# DAC_FMC_connector.net
KiCad netlist of a schematic drawn in Altium Designer
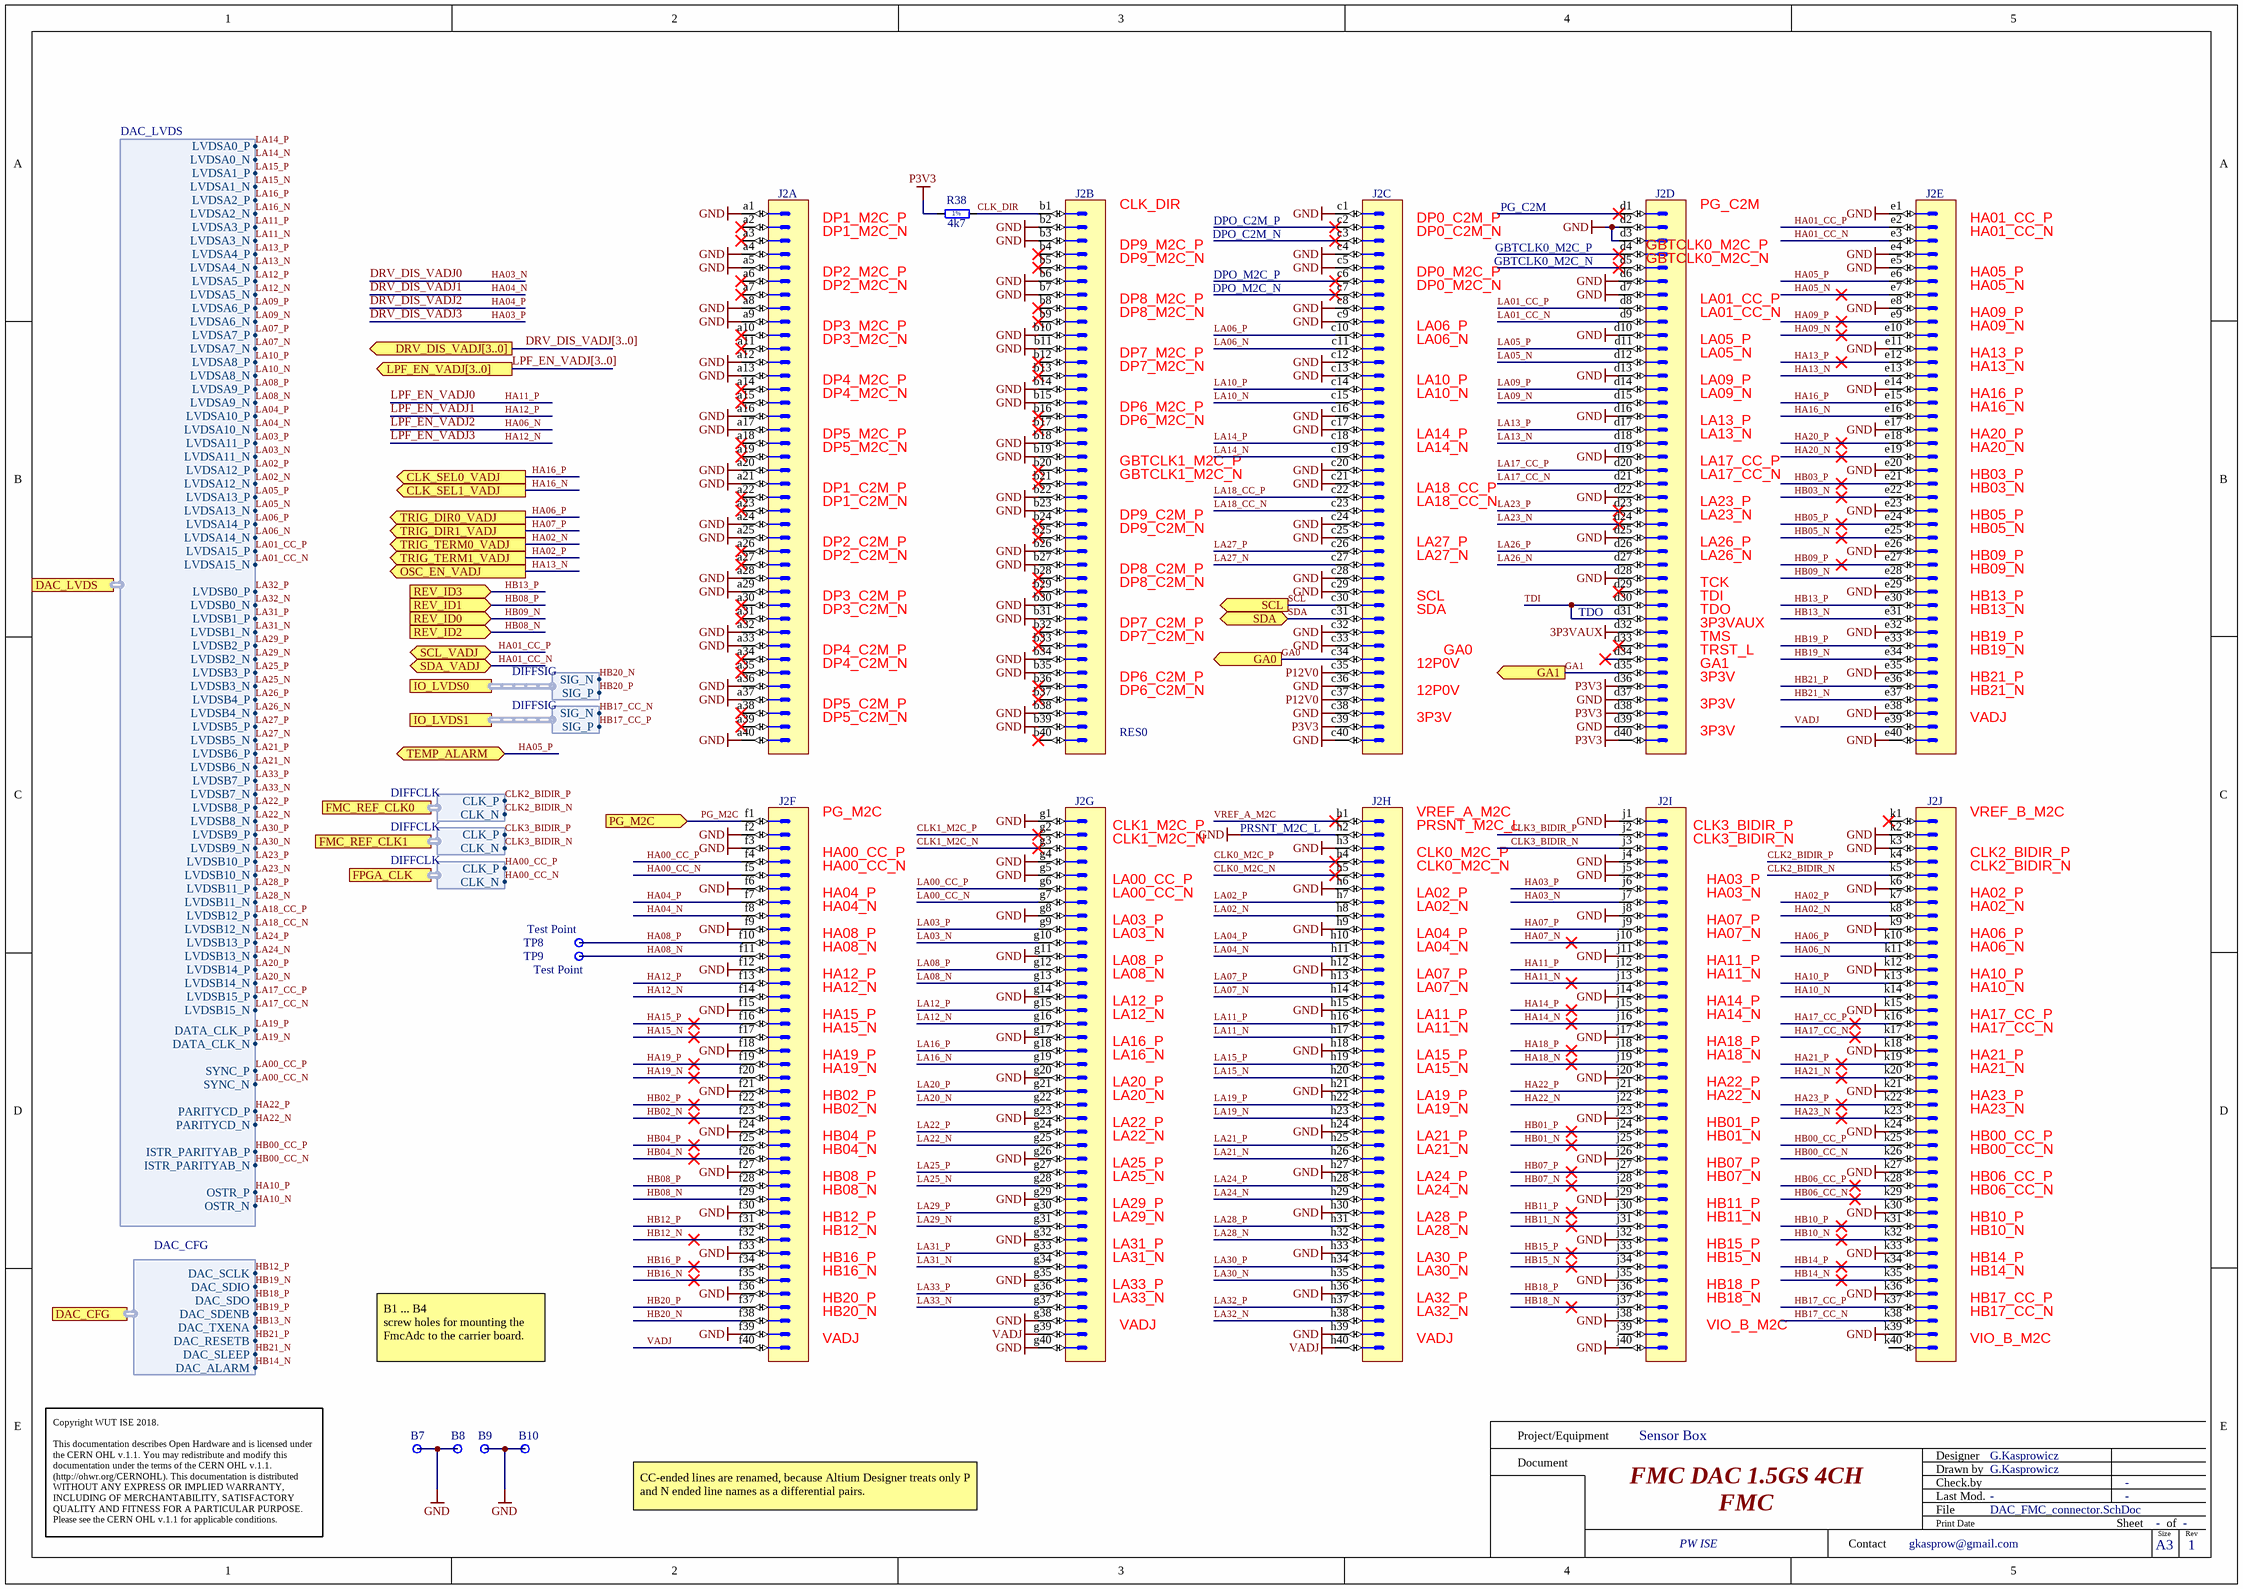
[diagram p0: DAC_FMC_connector.SchDoc]

(export (version "E")
  (design (tool "Eeschema 10.0.6"))
  (components
    (comp (ref "B7")
      (value "Plated Hole")
      (footprint "MTG300_600")
      (description "Single Terminal Socket")
      (fields (field (name "PART NUMBER") "PLATED_HOLE3.0_PAD6.0") (field (name "AUTHOR") "CERN DEM JLC"))
      (libsource (lib "Eletro-mechanical") (part "Single Terminal Socket"))
    )
    (comp (ref "B8")
      (value "Plated Hole")
      (footprint "MTG300_600")
      (description "Single Terminal Socket")
      (fields (field (name "PART NUMBER") "PLATED_HOLE3.0_PAD6.0") (field (name "AUTHOR") "CERN DEM JLC"))
      (libsource (lib "Eletro-mechanical") (part "Single Terminal Socket"))
    )
    (comp (ref "B9")
      (value "Plated Hole")
      (footprint "MTG300_600")
      (description "Single Terminal Socket")
      (fields (field (name "PART NUMBER") "PLATED_HOLE3.0_PAD6.0") (field (name "AUTHOR") "CERN DEM JLC"))
      (libsource (lib "Eletro-mechanical") (part "Single Terminal Socket"))
    )
    (comp (ref "B10")
      (value "Plated Hole")
      (footprint "MTG300_600")
      (description "Single Terminal Socket")
      (fields (field (name "PART NUMBER") "PLATED_HOLE3.0_PAD6.0") (field (name "AUTHOR") "CERN DEM JLC"))
      (libsource (lib "Eletro-mechanical") (part "Single Terminal Socket"))
    )
    (comp (ref "J2")
      (value "VITA 57")
      (footprint "SAMTEC_ASP-134488-01")
      (description "Connector VITA 57, 400 Male contacts in 10 row abcdefghj")
      (fields
        (field (name "PART NUMBER") "SAMTEC_ASP-134488-01")
        (field (name "MANUFACTURER") "SAMTEC")
        (field (name "AUTHOR") "CERN DEM JLC")
      )
      (libsource (lib "Connectors") (part "Connector VITA 57 400 Male (abcdefghjk)"))
    )
    (comp (ref "R38")
      (value "4k7")
      (footprint "RESC1608X55N")
      (description "Resistor - 1%")
      (fields
        (field (name "PART NUMBER") "R0603_4K7_1%_0.1W_100PPM")
        (field (name "POWER") "0.1W")
        (field (name "AUTHOR") "CERN DEM JLC")
      )
      (libsource (lib "Resistors") (part "Resistor - 1%"))
    )
    (comp (ref "TP8")
      (value "Test Point")
      (footprint "TPS127")
      (fields (field (name "PART NUMBER") "SMD_PAD_1.27X1.27MM") (field (name "AUTHOR") "CERN DEM JLC"))
      (libsource (lib "Eletro-mechanical") (part "Test Point"))
    )
    (comp (ref "TP9")
      (value "Test Point")
      (footprint "TPS127")
      (fields (field (name "PART NUMBER") "SMD_PAD_1.27X1.27MM") (field (name "AUTHOR") "CERN DEM JLC"))
      (libsource (lib "Eletro-mechanical") (part "Test Point"))
    )
  )
  (nets
    (net (code "5") (name "/CLK0_M2C_N") (class "Default")
      (node (ref "J2") (pin "h5") (pinfunction "h5_h5") (pintype "bidirectional+no_connect"))
    )
    (net (code "6") (name "/CLK0_M2C_P") (class "Default")
      (node (ref "J2") (pin "h4") (pinfunction "h4_h4") (pintype "bidirectional+no_connect"))
    )
    (net (code "7") (name "/CLK1_M2C_N") (class "Default")
      (node (ref "J2") (pin "g3") (pinfunction "g3_g3") (pintype "bidirectional+no_connect"))
    )
    (net (code "8") (name "/CLK1_M2C_P") (class "Default")
      (node (ref "J2") (pin "g2") (pinfunction "g2_g2") (pintype "bidirectional+no_connect"))
    )
    (net (code "9") (name "/CLK2_BIDIR_N") (class "Default")
      (node (ref "J2") (pin "k5") (pinfunction "k5_k5") (pintype "bidirectional"))
    )
    (net (code "10") (name "/CLK2_BIDIR_P") (class "Default")
      (node (ref "J2") (pin "k4") (pinfunction "k4_k4") (pintype "bidirectional"))
    )
    (net (code "11") (name "/CLK3_BIDIR_N") (class "Default")
      (node (ref "J2") (pin "j3") (pinfunction "j3_j3") (pintype "bidirectional"))
    )
    (net (code "12") (name "/CLK3_BIDIR_P") (class "Default")
      (node (ref "J2") (pin "j2") (pinfunction "j2_j2") (pintype "bidirectional"))
    )
    (net (code "13") (name "/CLK_DIR") (class "Default")
      (node (ref "J2") (pin "b1") (pinfunction "b1_b1") (pintype "bidirectional"))
      (node (ref "R38") (pin "2") (pinfunction "2_2") (pintype "passive"))
    )
    (net (code "14") (name "/DRV_DIS_VADJ0") (class "Default")
      (node (ref "J2") (pin "j7") (pinfunction "j7_j7") (pintype "bidirectional"))
    )
    (net (code "15") (name "/DRV_DIS_VADJ1") (class "Default")
      (node (ref "J2") (pin "f8") (pinfunction "f8_f8") (pintype "bidirectional"))
    )
    (net (code "16") (name "/DRV_DIS_VADJ2") (class "Default")
      (node (ref "J2") (pin "f7") (pinfunction "f7_f7") (pintype "bidirectional"))
    )
    (net (code "17") (name "/DRV_DIS_VADJ3") (class "Default")
      (node (ref "J2") (pin "j6") (pinfunction "j6_j6") (pintype "bidirectional"))
    )
    (net (code "19") (name "/GA0") (class "Default")
      (node (ref "J2") (pin "c34") (pinfunction "c34_c34") (pintype "bidirectional"))
    )
    (net (code "20") (name "/GA1") (class "Default")
      (node (ref "J2") (pin "d35") (pinfunction "d35_d35") (pintype "bidirectional"))
    )
    (net (code "21") (name "/HA00_CC_N") (class "Default")
      (node (ref "J2") (pin "f5") (pinfunction "f5_f5") (pintype "bidirectional"))
    )
    (net (code "22") (name "/HA00_CC_P") (class "Default")
      (node (ref "J2") (pin "f4") (pinfunction "f4_f4") (pintype "bidirectional"))
    )
    (net (code "23") (name "/HA01_CC_N") (class "Default")
      (node (ref "J2") (pin "e3") (pinfunction "e3_e3") (pintype "bidirectional"))
    )
    (net (code "24") (name "/HA01_CC_P") (class "Default")
      (node (ref "J2") (pin "e2") (pinfunction "e2_e2") (pintype "bidirectional"))
    )
    (net (code "25") (name "/HA02_N") (class "Default")
      (node (ref "J2") (pin "k8") (pinfunction "k8_k8") (pintype "bidirectional"))
    )
    (net (code "26") (name "/HA02_P") (class "Default")
      (node (ref "J2") (pin "k7") (pinfunction "k7_k7") (pintype "bidirectional"))
    )
    (net (code "27") (name "/HA05_N") (class "Default")
      (node (ref "J2") (pin "e7") (pinfunction "e7_e7") (pintype "bidirectional"))
    )
    (net (code "28") (name "/HA05_P") (class "Default")
      (node (ref "J2") (pin "e6") (pinfunction "e6_e6") (pintype "bidirectional"))
    )
    (net (code "29") (name "/HA06_P") (class "Default")
      (node (ref "J2") (pin "k10") (pinfunction "k10_k10") (pintype "bidirectional"))
    )
    (net (code "30") (name "/HA07_N") (class "Default")
      (node (ref "J2") (pin "j10") (pinfunction "j10_j10") (pintype "bidirectional"))
    )
    (net (code "31") (name "/HA07_P") (class "Default")
      (node (ref "J2") (pin "j9") (pinfunction "j9_j9") (pintype "bidirectional"))
    )
    (net (code "32") (name "/HA08_N") (class "Default")
      (node (ref "J2") (pin "f11") (pinfunction "f11_f11") (pintype "bidirectional"))
      (node (ref "TP9") (pin "1") (pinfunction "1_1") (pintype "bidirectional"))
    )
    (net (code "33") (name "/HA08_P") (class "Default")
      (node (ref "J2") (pin "f10") (pinfunction "f10_f10") (pintype "bidirectional"))
      (node (ref "TP8") (pin "1") (pinfunction "1_1") (pintype "bidirectional"))
    )
    (net (code "34") (name "/HA09_N") (class "Default")
      (node (ref "J2") (pin "e10") (pinfunction "e10_e10") (pintype "bidirectional"))
    )
    (net (code "35") (name "/HA09_P") (class "Default")
      (node (ref "J2") (pin "e9") (pinfunction "e9_e9") (pintype "bidirectional"))
    )
    (net (code "36") (name "/HA10_N") (class "Default")
      (node (ref "J2") (pin "k14") (pinfunction "k14_k14") (pintype "bidirectional"))
    )
    (net (code "37") (name "/HA10_P") (class "Default")
      (node (ref "J2") (pin "k13") (pinfunction "k13_k13") (pintype "bidirectional"))
    )
    (net (code "38") (name "/HA11_N") (class "Default")
      (node (ref "J2") (pin "j13") (pinfunction "j13_j13") (pintype "bidirectional"))
    )
    (net (code "39") (name "/HA13_N") (class "Default")
      (node (ref "J2") (pin "e13") (pinfunction "e13_e13") (pintype "bidirectional"))
    )
    (net (code "40") (name "/HA13_P") (class "Default")
      (node (ref "J2") (pin "e12") (pinfunction "e12_e12") (pintype "bidirectional"))
    )
    (net (code "41") (name "/HA14_N") (class "Default")
      (node (ref "J2") (pin "j16") (pinfunction "j16_j16") (pintype "bidirectional"))
    )
    (net (code "42") (name "/HA14_P") (class "Default")
      (node (ref "J2") (pin "j15") (pinfunction "j15_j15") (pintype "bidirectional"))
    )
    (net (code "43") (name "/HA15_N") (class "Default")
      (node (ref "J2") (pin "f17") (pinfunction "f17_f17") (pintype "bidirectional"))
    )
    (net (code "44") (name "/HA15_P") (class "Default")
      (node (ref "J2") (pin "f16") (pinfunction "f16_f16") (pintype "bidirectional"))
    )
    (net (code "45") (name "/HA16_N") (class "Default")
      (node (ref "J2") (pin "e16") (pinfunction "e16_e16") (pintype "bidirectional"))
    )
    (net (code "46") (name "/HA16_P") (class "Default")
      (node (ref "J2") (pin "e15") (pinfunction "e15_e15") (pintype "bidirectional"))
    )
    (net (code "47") (name "/HA17_CC_N") (class "Default")
      (node (ref "J2") (pin "k17") (pinfunction "k17_k17") (pintype "bidirectional"))
    )
    (net (code "48") (name "/HA17_CC_P") (class "Default")
      (node (ref "J2") (pin "k16") (pinfunction "k16_k16") (pintype "bidirectional"))
    )
    (net (code "49") (name "/HA18_N") (class "Default")
      (node (ref "J2") (pin "j19") (pinfunction "j19_j19") (pintype "bidirectional"))
    )
    (net (code "50") (name "/HA18_P") (class "Default")
      (node (ref "J2") (pin "j18") (pinfunction "j18_j18") (pintype "bidirectional"))
    )
    (net (code "51") (name "/HA19_N") (class "Default")
      (node (ref "J2") (pin "f20") (pinfunction "f20_f20") (pintype "bidirectional"))
    )
    (net (code "52") (name "/HA19_P") (class "Default")
      (node (ref "J2") (pin "f19") (pinfunction "f19_f19") (pintype "bidirectional"))
    )
    (net (code "53") (name "/HA20_N") (class "Default")
      (node (ref "J2") (pin "e19") (pinfunction "e19_e19") (pintype "bidirectional"))
    )
    (net (code "54") (name "/HA20_P") (class "Default")
      (node (ref "J2") (pin "e18") (pinfunction "e18_e18") (pintype "bidirectional"))
    )
    (net (code "55") (name "/HA21_N") (class "Default")
      (node (ref "J2") (pin "k20") (pinfunction "k20_k20") (pintype "bidirectional"))
    )
    (net (code "56") (name "/HA21_P") (class "Default")
      (node (ref "J2") (pin "k19") (pinfunction "k19_k19") (pintype "bidirectional"))
    )
    (net (code "57") (name "/HA22_N") (class "Default")
      (node (ref "J2") (pin "j22") (pinfunction "j22_j22") (pintype "bidirectional"))
    )
    (net (code "58") (name "/HA22_P") (class "Default")
      (node (ref "J2") (pin "j21") (pinfunction "j21_j21") (pintype "bidirectional"))
    )
    (net (code "59") (name "/HA23_N") (class "Default")
      (node (ref "J2") (pin "k23") (pinfunction "k23_k23") (pintype "bidirectional"))
    )
    (net (code "60") (name "/HA23_P") (class "Default")
      (node (ref "J2") (pin "k22") (pinfunction "k22_k22") (pintype "bidirectional"))
    )
    (net (code "61") (name "/HB00_CC_N") (class "Default")
      (node (ref "J2") (pin "k26") (pinfunction "k26_k26") (pintype "bidirectional"))
    )
    (net (code "62") (name "/HB00_CC_P") (class "Default")
      (node (ref "J2") (pin "k25") (pinfunction "k25_k25") (pintype "bidirectional"))
    )
    (net (code "63") (name "/HB01_N") (class "Default")
      (node (ref "J2") (pin "j25") (pinfunction "j25_j25") (pintype "bidirectional"))
    )
    (net (code "64") (name "/HB01_P") (class "Default")
      (node (ref "J2") (pin "j24") (pinfunction "j24_j24") (pintype "bidirectional"))
    )
    (net (code "65") (name "/HB02_N") (class "Default")
      (node (ref "J2") (pin "f23") (pinfunction "f23_f23") (pintype "bidirectional"))
    )
    (net (code "66") (name "/HB02_P") (class "Default")
      (node (ref "J2") (pin "f22") (pinfunction "f22_f22") (pintype "bidirectional"))
    )
    (net (code "67") (name "/HB03_N") (class "Default")
      (node (ref "J2") (pin "e22") (pinfunction "e22_e22") (pintype "bidirectional"))
    )
    (net (code "68") (name "/HB03_P") (class "Default")
      (node (ref "J2") (pin "e21") (pinfunction "e21_e21") (pintype "bidirectional"))
    )
    (net (code "69") (name "/HB04_N") (class "Default")
      (node (ref "J2") (pin "f26") (pinfunction "f26_f26") (pintype "bidirectional"))
    )
    (net (code "70") (name "/HB04_P") (class "Default")
      (node (ref "J2") (pin "f25") (pinfunction "f25_f25") (pintype "bidirectional"))
    )
    (net (code "71") (name "/HB05_N") (class "Default")
      (node (ref "J2") (pin "e25") (pinfunction "e25_e25") (pintype "bidirectional"))
    )
    (net (code "72") (name "/HB05_P") (class "Default")
      (node (ref "J2") (pin "e24") (pinfunction "e24_e24") (pintype "bidirectional"))
    )
    (net (code "73") (name "/HB06_CC_N") (class "Default")
      (node (ref "J2") (pin "k29") (pinfunction "k29_k29") (pintype "bidirectional"))
    )
    (net (code "74") (name "/HB06_CC_P") (class "Default")
      (node (ref "J2") (pin "k28") (pinfunction "k28_k28") (pintype "bidirectional"))
    )
    (net (code "75") (name "/HB07_N") (class "Default")
      (node (ref "J2") (pin "j28") (pinfunction "j28_j28") (pintype "bidirectional"))
    )
    (net (code "76") (name "/HB07_P") (class "Default")
      (node (ref "J2") (pin "j27") (pinfunction "j27_j27") (pintype "bidirectional"))
    )
    (net (code "77") (name "/HB08_N") (class "Default")
      (node (ref "J2") (pin "f29") (pinfunction "f29_f29") (pintype "bidirectional"))
    )
    (net (code "78") (name "/HB08_P") (class "Default")
      (node (ref "J2") (pin "f28") (pinfunction "f28_f28") (pintype "bidirectional"))
    )
    (net (code "79") (name "/HB09_N") (class "Default")
      (node (ref "J2") (pin "e28") (pinfunction "e28_e28") (pintype "bidirectional"))
    )
    (net (code "80") (name "/HB09_P") (class "Default")
      (node (ref "J2") (pin "e27") (pinfunction "e27_e27") (pintype "bidirectional"))
    )
    (net (code "81") (name "/HB10_N") (class "Default")
      (node (ref "J2") (pin "k32") (pinfunction "k32_k32") (pintype "bidirectional"))
    )
    (net (code "82") (name "/HB10_P") (class "Default")
      (node (ref "J2") (pin "k31") (pinfunction "k31_k31") (pintype "bidirectional"))
    )
    (net (code "83") (name "/HB11_N") (class "Default")
      (node (ref "J2") (pin "j31") (pinfunction "j31_j31") (pintype "bidirectional"))
    )
    (net (code "84") (name "/HB11_P") (class "Default")
      (node (ref "J2") (pin "j30") (pinfunction "j30_j30") (pintype "bidirectional"))
    )
    (net (code "85") (name "/HB12_N") (class "Default")
      (node (ref "J2") (pin "f32") (pinfunction "f32_f32") (pintype "bidirectional"))
    )
    (net (code "86") (name "/HB12_P") (class "Default")
      (node (ref "J2") (pin "f31") (pinfunction "f31_f31") (pintype "bidirectional"))
    )
    (net (code "87") (name "/HB13_N") (class "Default")
      (node (ref "J2") (pin "e31") (pinfunction "e31_e31") (pintype "bidirectional"))
    )
    (net (code "88") (name "/HB13_P") (class "Default")
      (node (ref "J2") (pin "e30") (pinfunction "e30_e30") (pintype "bidirectional"))
    )
    (net (code "89") (name "/HB14_N") (class "Default")
      (node (ref "J2") (pin "k35") (pinfunction "k35_k35") (pintype "bidirectional"))
    )
    (net (code "90") (name "/HB14_P") (class "Default")
      (node (ref "J2") (pin "k34") (pinfunction "k34_k34") (pintype "bidirectional"))
    )
    (net (code "91") (name "/HB15_N") (class "Default")
      (node (ref "J2") (pin "j34") (pinfunction "j34_j34") (pintype "bidirectional"))
    )
    (net (code "92") (name "/HB15_P") (class "Default")
      (node (ref "J2") (pin "j33") (pinfunction "j33_j33") (pintype "bidirectional"))
    )
    (net (code "93") (name "/HB16_N") (class "Default")
      (node (ref "J2") (pin "f35") (pinfunction "f35_f35") (pintype "bidirectional"))
    )
    (net (code "94") (name "/HB16_P") (class "Default")
      (node (ref "J2") (pin "f34") (pinfunction "f34_f34") (pintype "bidirectional"))
    )
    (net (code "95") (name "/HB17_CC_N") (class "Default")
      (node (ref "J2") (pin "k38") (pinfunction "k38_k38") (pintype "bidirectional"))
    )
    (net (code "96") (name "/HB17_CC_P") (class "Default")
      (node (ref "J2") (pin "k37") (pinfunction "k37_k37") (pintype "bidirectional"))
    )
    (net (code "97") (name "/HB18_N") (class "Default")
      (node (ref "J2") (pin "j37") (pinfunction "j37_j37") (pintype "bidirectional"))
    )
    (net (code "98") (name "/HB18_P") (class "Default")
      (node (ref "J2") (pin "j36") (pinfunction "j36_j36") (pintype "bidirectional"))
    )
    (net (code "99") (name "/HB19_N") (class "Default")
      (node (ref "J2") (pin "e34") (pinfunction "e34_e34") (pintype "bidirectional"))
    )
    (net (code "100") (name "/HB19_P") (class "Default")
      (node (ref "J2") (pin "e33") (pinfunction "e33_e33") (pintype "bidirectional"))
    )
    (net (code "101") (name "/HB20_N") (class "Default")
      (node (ref "J2") (pin "f38") (pinfunction "f38_f38") (pintype "bidirectional"))
    )
    (net (code "102") (name "/HB20_P") (class "Default")
      (node (ref "J2") (pin "f37") (pinfunction "f37_f37") (pintype "bidirectional"))
    )
    (net (code "103") (name "/HB21_N") (class "Default")
      (node (ref "J2") (pin "e37") (pinfunction "e37_e37") (pintype "bidirectional"))
    )
    (net (code "104") (name "/HB21_P") (class "Default")
      (node (ref "J2") (pin "e36") (pinfunction "e36_e36") (pintype "bidirectional"))
    )
    (net (code "105") (name "/LA00_CC_N") (class "Default")
      (node (ref "J2") (pin "g7") (pinfunction "g7_g7") (pintype "bidirectional"))
    )
    (net (code "106") (name "/LA00_CC_P") (class "Default")
      (node (ref "J2") (pin "g6") (pinfunction "g6_g6") (pintype "bidirectional"))
    )
    (net (code "107") (name "/LA01_CC_N") (class "Default")
      (node (ref "J2") (pin "d9") (pinfunction "d9_d9") (pintype "bidirectional"))
    )
    (net (code "108") (name "/LA01_CC_P") (class "Default")
      (node (ref "J2") (pin "d8") (pinfunction "d8_d8") (pintype "bidirectional"))
    )
    (net (code "109") (name "/LA02_N") (class "Default")
      (node (ref "J2") (pin "h8") (pinfunction "h8_h8") (pintype "bidirectional"))
    )
    (net (code "110") (name "/LA02_P") (class "Default")
      (node (ref "J2") (pin "h7") (pinfunction "h7_h7") (pintype "bidirectional"))
    )
    (net (code "111") (name "/LA03_N") (class "Default")
      (node (ref "J2") (pin "g10") (pinfunction "g10_g10") (pintype "bidirectional"))
    )
    (net (code "112") (name "/LA03_P") (class "Default")
      (node (ref "J2") (pin "g9") (pinfunction "g9_g9") (pintype "bidirectional"))
    )
    (net (code "113") (name "/LA04_N") (class "Default")
      (node (ref "J2") (pin "h11") (pinfunction "h11_h11") (pintype "bidirectional"))
    )
    (net (code "114") (name "/LA04_P") (class "Default")
      (node (ref "J2") (pin "h10") (pinfunction "h10_h10") (pintype "bidirectional"))
    )
    (net (code "115") (name "/LA05_N") (class "Default")
      (node (ref "J2") (pin "d12") (pinfunction "d12_d12") (pintype "bidirectional"))
    )
    (net (code "116") (name "/LA05_P") (class "Default")
      (node (ref "J2") (pin "d11") (pinfunction "d11_d11") (pintype "bidirectional"))
    )
    (net (code "117") (name "/LA06_N") (class "Default")
      (node (ref "J2") (pin "c11") (pinfunction "c11_c11") (pintype "bidirectional"))
    )
    (net (code "118") (name "/LA06_P") (class "Default")
      (node (ref "J2") (pin "c10") (pinfunction "c10_c10") (pintype "bidirectional"))
    )
    (net (code "119") (name "/LA07_N") (class "Default")
      (node (ref "J2") (pin "h14") (pinfunction "h14_h14") (pintype "bidirectional"))
    )
    (net (code "120") (name "/LA07_P") (class "Default")
      (node (ref "J2") (pin "h13") (pinfunction "h13_h13") (pintype "bidirectional"))
    )
    (net (code "121") (name "/LA08_N") (class "Default")
      (node (ref "J2") (pin "g13") (pinfunction "g13_g13") (pintype "bidirectional"))
    )
    (net (code "122") (name "/LA08_P") (class "Default")
      (node (ref "J2") (pin "g12") (pinfunction "g12_g12") (pintype "bidirectional"))
    )
    (net (code "123") (name "/LA09_N") (class "Default")
      (node (ref "J2") (pin "d15") (pinfunction "d15_d15") (pintype "bidirectional"))
    )
    (net (code "124") (name "/LA09_P") (class "Default")
      (node (ref "J2") (pin "d14") (pinfunction "d14_d14") (pintype "bidirectional"))
    )
    (net (code "125") (name "/LA10_N") (class "Default")
      (node (ref "J2") (pin "c15") (pinfunction "c15_c15") (pintype "bidirectional"))
    )
    (net (code "126") (name "/LA10_P") (class "Default")
      (node (ref "J2") (pin "c14") (pinfunction "c14_c14") (pintype "bidirectional"))
    )
    (net (code "127") (name "/LA11_N") (class "Default")
      (node (ref "J2") (pin "h17") (pinfunction "h17_h17") (pintype "bidirectional"))
    )
    (net (code "128") (name "/LA11_P") (class "Default")
      (node (ref "J2") (pin "h16") (pinfunction "h16_h16") (pintype "bidirectional"))
    )
    (net (code "129") (name "/LA12_N") (class "Default")
      (node (ref "J2") (pin "g16") (pinfunction "g16_g16") (pintype "bidirectional"))
    )
    (net (code "130") (name "/LA12_P") (class "Default")
      (node (ref "J2") (pin "g15") (pinfunction "g15_g15") (pintype "bidirectional"))
    )
    (net (code "131") (name "/LA13_N") (class "Default")
      (node (ref "J2") (pin "d18") (pinfunction "d18_d18") (pintype "bidirectional"))
    )
    (net (code "132") (name "/LA13_P") (class "Default")
      (node (ref "J2") (pin "d17") (pinfunction "d17_d17") (pintype "bidirectional"))
    )
    (net (code "133") (name "/LA14_N") (class "Default")
      (node (ref "J2") (pin "c19") (pinfunction "c19_c19") (pintype "bidirectional"))
    )
    (net (code "134") (name "/LA14_P") (class "Default")
      (node (ref "J2") (pin "c18") (pinfunction "c18_c18") (pintype "bidirectional"))
    )
    (net (code "135") (name "/LA15_N") (class "Default")
      (node (ref "J2") (pin "h20") (pinfunction "h20_h20") (pintype "bidirectional"))
    )
    (net (code "136") (name "/LA15_P") (class "Default")
      (node (ref "J2") (pin "h19") (pinfunction "h19_h19") (pintype "bidirectional"))
    )
    (net (code "137") (name "/LA16_N") (class "Default")
      (node (ref "J2") (pin "g19") (pinfunction "g19_g19") (pintype "bidirectional"))
    )
    (net (code "138") (name "/LA16_P") (class "Default")
      (node (ref "J2") (pin "g18") (pinfunction "g18_g18") (pintype "bidirectional"))
    )
    (net (code "139") (name "/LA17_CC_N") (class "Default")
      (node (ref "J2") (pin "d21") (pinfunction "d21_d21") (pintype "bidirectional"))
    )
    (net (code "140") (name "/LA17_CC_P") (class "Default")
      (node (ref "J2") (pin "d20") (pinfunction "d20_d20") (pintype "bidirectional"))
    )
    (net (code "141") (name "/LA18_CC_N") (class "Default")
      (node (ref "J2") (pin "c23") (pinfunction "c23_c23") (pintype "bidirectional"))
    )
    (net (code "142") (name "/LA18_CC_P") (class "Default")
      (node (ref "J2") (pin "c22") (pinfunction "c22_c22") (pintype "bidirectional"))
    )
    (net (code "143") (name "/LA19_N") (class "Default")
      (node (ref "J2") (pin "h23") (pinfunction "h23_h23") (pintype "bidirectional"))
    )
    (net (code "144") (name "/LA19_P") (class "Default")
      (node (ref "J2") (pin "h22") (pinfunction "h22_h22") (pintype "bidirectional"))
    )
    (net (code "145") (name "/LA20_N") (class "Default")
      (node (ref "J2") (pin "g22") (pinfunction "g22_g22") (pintype "bidirectional"))
    )
    (net (code "146") (name "/LA20_P") (class "Default")
      (node (ref "J2") (pin "g21") (pinfunction "g21_g21") (pintype "bidirectional"))
    )
    (net (code "147") (name "/LA21_N") (class "Default")
      (node (ref "J2") (pin "h26") (pinfunction "h26_h26") (pintype "bidirectional"))
    )
    (net (code "148") (name "/LA21_P") (class "Default")
      (node (ref "J2") (pin "h25") (pinfunction "h25_h25") (pintype "bidirectional"))
    )
    (net (code "149") (name "/LA22_N") (class "Default")
      (node (ref "J2") (pin "g25") (pinfunction "g25_g25") (pintype "bidirectional"))
    )
    (net (code "150") (name "/LA22_P") (class "Default")
      (node (ref "J2") (pin "g24") (pinfunction "g24_g24") (pintype "bidirectional"))
    )
    (net (code "151") (name "/LA23_N") (class "Default")
      (node (ref "J2") (pin "d24") (pinfunction "d24_d24") (pintype "bidirectional"))
    )
    (net (code "152") (name "/LA23_P") (class "Default")
      (node (ref "J2") (pin "d23") (pinfunction "d23_d23") (pintype "bidirectional"))
    )
    (net (code "153") (name "/LA24_N") (class "Default")
      (node (ref "J2") (pin "h29") (pinfunction "h29_h29") (pintype "bidirectional"))
    )
    (net (code "154") (name "/LA24_P") (class "Default")
      (node (ref "J2") (pin "h28") (pinfunction "h28_h28") (pintype "bidirectional"))
    )
    (net (code "155") (name "/LA25_N") (class "Default")
      (node (ref "J2") (pin "g28") (pinfunction "g28_g28") (pintype "bidirectional"))
    )
    (net (code "156") (name "/LA25_P") (class "Default")
      (node (ref "J2") (pin "g27") (pinfunction "g27_g27") (pintype "bidirectional"))
    )
    (net (code "157") (name "/LA26_N") (class "Default")
      (node (ref "J2") (pin "d27") (pinfunction "d27_d27") (pintype "bidirectional"))
    )
    (net (code "158") (name "/LA26_P") (class "Default")
      (node (ref "J2") (pin "d26") (pinfunction "d26_d26") (pintype "bidirectional"))
    )
    (net (code "159") (name "/LA27_N") (class "Default")
      (node (ref "J2") (pin "c27") (pinfunction "c27_c27") (pintype "bidirectional"))
    )
    (net (code "160") (name "/LA27_P") (class "Default")
      (node (ref "J2") (pin "c26") (pinfunction "c26_c26") (pintype "bidirectional"))
    )
    (net (code "161") (name "/LA28_N") (class "Default")
      (node (ref "J2") (pin "h32") (pinfunction "h32_h32") (pintype "bidirectional"))
    )
    (net (code "162") (name "/LA28_P") (class "Default")
      (node (ref "J2") (pin "h31") (pinfunction "h31_h31") (pintype "bidirectional"))
    )
    (net (code "163") (name "/LA29_N") (class "Default")
      (node (ref "J2") (pin "g31") (pinfunction "g31_g31") (pintype "bidirectional"))
    )
    (net (code "164") (name "/LA29_P") (class "Default")
      (node (ref "J2") (pin "g30") (pinfunction "g30_g30") (pintype "bidirectional"))
    )
    (net (code "165") (name "/LA30_N") (class "Default")
      (node (ref "J2") (pin "h35") (pinfunction "h35_h35") (pintype "bidirectional"))
    )
    (net (code "166") (name "/LA30_P") (class "Default")
      (node (ref "J2") (pin "h34") (pinfunction "h34_h34") (pintype "bidirectional"))
    )
    (net (code "167") (name "/LA31_N") (class "Default")
      (node (ref "J2") (pin "g34") (pinfunction "g34_g34") (pintype "bidirectional"))
    )
    (net (code "168") (name "/LA31_P") (class "Default")
      (node (ref "J2") (pin "g33") (pinfunction "g33_g33") (pintype "bidirectional"))
    )
    (net (code "169") (name "/LA32_N") (class "Default")
      (node (ref "J2") (pin "h38") (pinfunction "h38_h38") (pintype "bidirectional"))
    )
    (net (code "170") (name "/LA32_P") (class "Default")
      (node (ref "J2") (pin "h37") (pinfunction "h37_h37") (pintype "bidirectional"))
    )
    (net (code "171") (name "/LA33_N") (class "Default")
      (node (ref "J2") (pin "g37") (pinfunction "g37_g37") (pintype "bidirectional"))
    )
    (net (code "172") (name "/LA33_P") (class "Default")
      (node (ref "J2") (pin "g36") (pinfunction "g36_g36") (pintype "bidirectional"))
    )
    (net (code "173") (name "/LPF_EN_VADJ0") (class "Default")
      (node (ref "J2") (pin "j12") (pinfunction "j12_j12") (pintype "bidirectional"))
    )
    (net (code "174") (name "/LPF_EN_VADJ1") (class "Default")
      (node (ref "J2") (pin "f13") (pinfunction "f13_f13") (pintype "bidirectional"))
    )
    (net (code "175") (name "/LPF_EN_VADJ2") (class "Default")
      (node (ref "J2") (pin "k11") (pinfunction "k11_k11") (pintype "bidirectional"))
    )
    (net (code "176") (name "/LPF_EN_VADJ3") (class "Default")
      (node (ref "J2") (pin "f14") (pinfunction "f14_f14") (pintype "bidirectional"))
    )
    (net (code "178") (name "/PG_M2C") (class "Default")
      (node (ref "J2") (pin "f1") (pinfunction "f1_f1") (pintype "bidirectional"))
    )
    (net (code "179") (name "/SCL") (class "Default")
      (node (ref "J2") (pin "c30") (pinfunction "c30_c30") (pintype "bidirectional"))
    )
    (net (code "180") (name "/SDA") (class "Default")
      (node (ref "J2") (pin "c31") (pinfunction "c31_c31") (pintype "bidirectional"))
    )
    (net (code "181") (name "/TDI") (class "Default")
      (node (ref "J2") (pin "d30") (pinfunction "d30_d30") (pintype "bidirectional"))
      (node (ref "J2") (pin "d31") (pinfunction "d31_d31") (pintype "bidirectional"))
    )
    (net (code "182") (name "/VREF_A_M2C") (class "Default")
      (node (ref "J2") (pin "h1") (pinfunction "h1_h1") (pintype "bidirectional+no_connect"))
    )
    (net (code "187") (name "3P3VAUX") (class "Default")
      (node (ref "J2") (pin "d32") (pinfunction "d32_d32") (pintype "bidirectional"))
    )
    (net (code "188") (name "GND") (class "Default")
      (node (ref "B10") (pin "1") (pinfunction "1_1") (pintype "bidirectional"))
      (node (ref "B7") (pin "1") (pinfunction "1_1") (pintype "bidirectional"))
      (node (ref "B8") (pin "1") (pinfunction "1_1") (pintype "bidirectional"))
      (node (ref "B9") (pin "1") (pinfunction "1_1") (pintype "bidirectional"))
      (node (ref "J2") (pin "a1") (pinfunction "a1_a1") (pintype "bidirectional"))
      (node (ref "J2") (pin "a12") (pinfunction "a12_a12") (pintype "bidirectional"))
      (node (ref "J2") (pin "a13") (pinfunction "a13_a13") (pintype "bidirectional"))
      (node (ref "J2") (pin "a16") (pinfunction "a16_a16") (pintype "bidirectional"))
      (node (ref "J2") (pin "a17") (pinfunction "a17_a17") (pintype "bidirectional"))
      (node (ref "J2") (pin "a20") (pinfunction "a20_a20") (pintype "bidirectional"))
      (node (ref "J2") (pin "a21") (pinfunction "a21_a21") (pintype "bidirectional"))
      (node (ref "J2") (pin "a24") (pinfunction "a24_a24") (pintype "bidirectional"))
      (node (ref "J2") (pin "a25") (pinfunction "a25_a25") (pintype "bidirectional"))
      (node (ref "J2") (pin "a28") (pinfunction "a28_a28") (pintype "bidirectional"))
      (node (ref "J2") (pin "a29") (pinfunction "a29_a29") (pintype "bidirectional"))
      (node (ref "J2") (pin "a32") (pinfunction "a32_a32") (pintype "bidirectional"))
      (node (ref "J2") (pin "a33") (pinfunction "a33_a33") (pintype "bidirectional"))
      (node (ref "J2") (pin "a36") (pinfunction "a36_a36") (pintype "bidirectional"))
      (node (ref "J2") (pin "a37") (pinfunction "a37_a37") (pintype "bidirectional"))
      (node (ref "J2") (pin "a4") (pinfunction "a4_a4") (pintype "bidirectional"))
      (node (ref "J2") (pin "a40") (pinfunction "a40_a40") (pintype "bidirectional"))
      (node (ref "J2") (pin "a5") (pinfunction "a5_a5") (pintype "bidirectional"))
      (node (ref "J2") (pin "a8") (pinfunction "a8_a8") (pintype "bidirectional"))
      (node (ref "J2") (pin "a9") (pinfunction "a9_a9") (pintype "bidirectional"))
      (node (ref "J2") (pin "b10") (pinfunction "b10_b10") (pintype "bidirectional"))
      (node (ref "J2") (pin "b11") (pinfunction "b11_b11") (pintype "bidirectional"))
      (node (ref "J2") (pin "b14") (pinfunction "b14_b14") (pintype "bidirectional"))
      (node (ref "J2") (pin "b15") (pinfunction "b15_b15") (pintype "bidirectional"))
      (node (ref "J2") (pin "b18") (pinfunction "b18_b18") (pintype "bidirectional"))
      (node (ref "J2") (pin "b19") (pinfunction "b19_b19") (pintype "bidirectional"))
      (node (ref "J2") (pin "b2") (pinfunction "b2_b2") (pintype "bidirectional"))
      (node (ref "J2") (pin "b22") (pinfunction "b22_b22") (pintype "bidirectional"))
      (node (ref "J2") (pin "b23") (pinfunction "b23_b23") (pintype "bidirectional"))
      (node (ref "J2") (pin "b26") (pinfunction "b26_b26") (pintype "bidirectional"))
      (node (ref "J2") (pin "b27") (pinfunction "b27_b27") (pintype "bidirectional"))
      (node (ref "J2") (pin "b3") (pinfunction "b3_b3") (pintype "bidirectional"))
      (node (ref "J2") (pin "b30") (pinfunction "b30_b30") (pintype "bidirectional"))
      (node (ref "J2") (pin "b31") (pinfunction "b31_b31") (pintype "bidirectional"))
      (node (ref "J2") (pin "b34") (pinfunction "b34_b34") (pintype "bidirectional"))
      (node (ref "J2") (pin "b35") (pinfunction "b35_b35") (pintype "bidirectional"))
      (node (ref "J2") (pin "b38") (pinfunction "b38_b38") (pintype "bidirectional"))
      (node (ref "J2") (pin "b39") (pinfunction "b39_b39") (pintype "bidirectional"))
      (node (ref "J2") (pin "b6") (pinfunction "b6_b6") (pintype "bidirectional"))
      (node (ref "J2") (pin "b7") (pinfunction "b7_b7") (pintype "bidirectional"))
      (node (ref "J2") (pin "c1") (pinfunction "c1_c1") (pintype "bidirectional"))
      (node (ref "J2") (pin "c12") (pinfunction "c12_c12") (pintype "bidirectional"))
      (node (ref "J2") (pin "c13") (pinfunction "c13_c13") (pintype "bidirectional"))
      (node (ref "J2") (pin "c16") (pinfunction "c16_c16") (pintype "bidirectional"))
      (node (ref "J2") (pin "c17") (pinfunction "c17_c17") (pintype "bidirectional"))
      (node (ref "J2") (pin "c20") (pinfunction "c20_c20") (pintype "bidirectional"))
      (node (ref "J2") (pin "c21") (pinfunction "c21_c21") (pintype "bidirectional"))
      (node (ref "J2") (pin "c24") (pinfunction "c24_c24") (pintype "bidirectional"))
      (node (ref "J2") (pin "c25") (pinfunction "c25_c25") (pintype "bidirectional"))
      (node (ref "J2") (pin "c28") (pinfunction "c28_c28") (pintype "bidirectional"))
      (node (ref "J2") (pin "c29") (pinfunction "c29_c29") (pintype "bidirectional"))
      (node (ref "J2") (pin "c32") (pinfunction "c32_c32") (pintype "bidirectional"))
      (node (ref "J2") (pin "c33") (pinfunction "c33_c33") (pintype "bidirectional"))
      (node (ref "J2") (pin "c36") (pinfunction "c36_c36") (pintype "bidirectional"))
      (node (ref "J2") (pin "c38") (pinfunction "c38_c38") (pintype "bidirectional"))
      (node (ref "J2") (pin "c4") (pinfunction "c4_c4") (pintype "bidirectional"))
      (node (ref "J2") (pin "c40") (pinfunction "c40_c40") (pintype "bidirectional"))
      (node (ref "J2") (pin "c5") (pinfunction "c5_c5") (pintype "bidirectional"))
      (node (ref "J2") (pin "c8") (pinfunction "c8_c8") (pintype "bidirectional"))
      (node (ref "J2") (pin "c9") (pinfunction "c9_c9") (pintype "bidirectional"))
      (node (ref "J2") (pin "d10") (pinfunction "d10_d10") (pintype "bidirectional"))
      (node (ref "J2") (pin "d13") (pinfunction "d13_d13") (pintype "bidirectional"))
      (node (ref "J2") (pin "d16") (pinfunction "d16_d16") (pintype "bidirectional"))
      (node (ref "J2") (pin "d19") (pinfunction "d19_d19") (pintype "bidirectional"))
      (node (ref "J2") (pin "d2") (pinfunction "d2_d2") (pintype "bidirectional"))
      (node (ref "J2") (pin "d22") (pinfunction "d22_d22") (pintype "bidirectional"))
      (node (ref "J2") (pin "d25") (pinfunction "d25_d25") (pintype "bidirectional"))
      (node (ref "J2") (pin "d28") (pinfunction "d28_d28") (pintype "bidirectional"))
      (node (ref "J2") (pin "d3") (pinfunction "d3_d3") (pintype "bidirectional"))
      (node (ref "J2") (pin "d37") (pinfunction "d37_d37") (pintype "bidirectional"))
      (node (ref "J2") (pin "d39") (pinfunction "d39_d39") (pintype "bidirectional"))
      (node (ref "J2") (pin "d6") (pinfunction "d6_d6") (pintype "bidirectional"))
      (node (ref "J2") (pin "d7") (pinfunction "d7_d7") (pintype "bidirectional"))
      (node (ref "J2") (pin "e1") (pinfunction "e1_e1") (pintype "bidirectional"))
      (node (ref "J2") (pin "e11") (pinfunction "e11_e11") (pintype "bidirectional"))
      (node (ref "J2") (pin "e14") (pinfunction "e14_e14") (pintype "bidirectional"))
      (node (ref "J2") (pin "e17") (pinfunction "e17_e17") (pintype "bidirectional"))
      (node (ref "J2") (pin "e20") (pinfunction "e20_e20") (pintype "bidirectional"))
      (node (ref "J2") (pin "e23") (pinfunction "e23_e23") (pintype "bidirectional"))
      (node (ref "J2") (pin "e26") (pinfunction "e26_e26") (pintype "bidirectional"))
      (node (ref "J2") (pin "e29") (pinfunction "e29_e29") (pintype "bidirectional"))
      (node (ref "J2") (pin "e32") (pinfunction "e32_e32") (pintype "bidirectional"))
      (node (ref "J2") (pin "e35") (pinfunction "e35_e35") (pintype "bidirectional"))
      (node (ref "J2") (pin "e38") (pinfunction "e38_e38") (pintype "bidirectional"))
      (node (ref "J2") (pin "e4") (pinfunction "e4_e4") (pintype "bidirectional"))
      (node (ref "J2") (pin "e40") (pinfunction "e40_e40") (pintype "bidirectional"))
      (node (ref "J2") (pin "e5") (pinfunction "e5_e5") (pintype "bidirectional"))
      (node (ref "J2") (pin "e8") (pinfunction "e8_e8") (pintype "bidirectional"))
      (node (ref "J2") (pin "f12") (pinfunction "f12_f12") (pintype "bidirectional"))
      (node (ref "J2") (pin "f15") (pinfunction "f15_f15") (pintype "bidirectional"))
      (node (ref "J2") (pin "f18") (pinfunction "f18_f18") (pintype "bidirectional"))
      (node (ref "J2") (pin "f2") (pinfunction "f2_f2") (pintype "bidirectional"))
      (node (ref "J2") (pin "f21") (pinfunction "f21_f21") (pintype "bidirectional"))
      (node (ref "J2") (pin "f24") (pinfunction "f24_f24") (pintype "bidirectional"))
      (node (ref "J2") (pin "f27") (pinfunction "f27_f27") (pintype "bidirectional"))
      (node (ref "J2") (pin "f3") (pinfunction "f3_f3") (pintype "bidirectional"))
      (node (ref "J2") (pin "f30") (pinfunction "f30_f30") (pintype "bidirectional"))
      (node (ref "J2") (pin "f33") (pinfunction "f33_f33") (pintype "bidirectional"))
      (node (ref "J2") (pin "f36") (pinfunction "f36_f36") (pintype "bidirectional"))
      (node (ref "J2") (pin "f39") (pinfunction "f39_f39") (pintype "bidirectional"))
      (node (ref "J2") (pin "f6") (pinfunction "f6_f6") (pintype "bidirectional"))
      (node (ref "J2") (pin "f9") (pinfunction "f9_f9") (pintype "bidirectional"))
      (node (ref "J2") (pin "g1") (pinfunction "g1_g1") (pintype "bidirectional"))
      (node (ref "J2") (pin "g11") (pinfunction "g11_g11") (pintype "bidirectional"))
      (node (ref "J2") (pin "g14") (pinfunction "g14_g14") (pintype "bidirectional"))
      (node (ref "J2") (pin "g17") (pinfunction "g17_g17") (pintype "bidirectional"))
      (node (ref "J2") (pin "g20") (pinfunction "g20_g20") (pintype "bidirectional"))
      (node (ref "J2") (pin "g23") (pinfunction "g23_g23") (pintype "bidirectional"))
      (node (ref "J2") (pin "g26") (pinfunction "g26_g26") (pintype "bidirectional"))
      (node (ref "J2") (pin "g29") (pinfunction "g29_g29") (pintype "bidirectional"))
      (node (ref "J2") (pin "g32") (pinfunction "g32_g32") (pintype "bidirectional"))
      (node (ref "J2") (pin "g35") (pinfunction "g35_g35") (pintype "bidirectional"))
      (node (ref "J2") (pin "g38") (pinfunction "g38_g38") (pintype "bidirectional"))
      (node (ref "J2") (pin "g4") (pinfunction "g4_g4") (pintype "bidirectional"))
      (node (ref "J2") (pin "g40") (pinfunction "g40_g40") (pintype "bidirectional"))
      (node (ref "J2") (pin "g5") (pinfunction "g5_g5") (pintype "bidirectional"))
      (node (ref "J2") (pin "g8") (pinfunction "g8_g8") (pintype "bidirectional"))
      (node (ref "J2") (pin "h12") (pinfunction "h12_h12") (pintype "bidirectional"))
      (node (ref "J2") (pin "h15") (pinfunction "h15_h15") (pintype "bidirectional"))
      (node (ref "J2") (pin "h18") (pinfunction "h18_h18") (pintype "bidirectional"))
      (node (ref "J2") (pin "h2") (pinfunction "h2_h2") (pintype "bidirectional"))
      (node (ref "J2") (pin "h21") (pinfunction "h21_h21") (pintype "bidirectional"))
      (node (ref "J2") (pin "h24") (pinfunction "h24_h24") (pintype "bidirectional"))
      (node (ref "J2") (pin "h27") (pinfunction "h27_h27") (pintype "bidirectional"))
      (node (ref "J2") (pin "h3") (pinfunction "h3_h3") (pintype "bidirectional"))
      (node (ref "J2") (pin "h30") (pinfunction "h30_h30") (pintype "bidirectional"))
      (node (ref "J2") (pin "h33") (pinfunction "h33_h33") (pintype "bidirectional"))
      (node (ref "J2") (pin "h36") (pinfunction "h36_h36") (pintype "bidirectional"))
      (node (ref "J2") (pin "h39") (pinfunction "h39_h39") (pintype "bidirectional"))
      (node (ref "J2") (pin "h6") (pinfunction "h6_h6") (pintype "bidirectional"))
      (node (ref "J2") (pin "h9") (pinfunction "h9_h9") (pintype "bidirectional"))
      (node (ref "J2") (pin "j1") (pinfunction "j1_j1") (pintype "bidirectional"))
      (node (ref "J2") (pin "j11") (pinfunction "j11_j11") (pintype "bidirectional"))
      (node (ref "J2") (pin "j14") (pinfunction "j14_j14") (pintype "bidirectional"))
      (node (ref "J2") (pin "j17") (pinfunction "j17_j17") (pintype "bidirectional"))
      (node (ref "J2") (pin "j20") (pinfunction "j20_j20") (pintype "bidirectional"))
      (node (ref "J2") (pin "j23") (pinfunction "j23_j23") (pintype "bidirectional"))
      (node (ref "J2") (pin "j26") (pinfunction "j26_j26") (pintype "bidirectional"))
      (node (ref "J2") (pin "j29") (pinfunction "j29_j29") (pintype "bidirectional"))
      (node (ref "J2") (pin "j32") (pinfunction "j32_j32") (pintype "bidirectional"))
      (node (ref "J2") (pin "j35") (pinfunction "j35_j35") (pintype "bidirectional"))
      (node (ref "J2") (pin "j38") (pinfunction "j38_j38") (pintype "bidirectional"))
      (node (ref "J2") (pin "j4") (pinfunction "j4_j4") (pintype "bidirectional"))
      (node (ref "J2") (pin "j40") (pinfunction "j40_j40") (pintype "bidirectional"))
      (node (ref "J2") (pin "j5") (pinfunction "j5_j5") (pintype "bidirectional"))
      (node (ref "J2") (pin "j8") (pinfunction "j8_j8") (pintype "bidirectional"))
      (node (ref "J2") (pin "k12") (pinfunction "k12_k12") (pintype "bidirectional"))
      (node (ref "J2") (pin "k15") (pinfunction "k15_k15") (pintype "bidirectional"))
      (node (ref "J2") (pin "k18") (pinfunction "k18_k18") (pintype "bidirectional"))
      (node (ref "J2") (pin "k2") (pinfunction "k2_k2") (pintype "bidirectional"))
      (node (ref "J2") (pin "k21") (pinfunction "k21_k21") (pintype "bidirectional"))
      (node (ref "J2") (pin "k24") (pinfunction "k24_k24") (pintype "bidirectional"))
      (node (ref "J2") (pin "k27") (pinfunction "k27_k27") (pintype "bidirectional"))
      (node (ref "J2") (pin "k3") (pinfunction "k3_k3") (pintype "bidirectional"))
      (node (ref "J2") (pin "k30") (pinfunction "k30_k30") (pintype "bidirectional"))
      (node (ref "J2") (pin "k33") (pinfunction "k33_k33") (pintype "bidirectional"))
      (node (ref "J2") (pin "k36") (pinfunction "k36_k36") (pintype "bidirectional"))
      (node (ref "J2") (pin "k39") (pinfunction "k39_k39") (pintype "bidirectional"))
      (node (ref "J2") (pin "k6") (pinfunction "k6_k6") (pintype "bidirectional"))
      (node (ref "J2") (pin "k9") (pinfunction "k9_k9") (pintype "bidirectional"))
    )
    (net (code "189") (name "P3V3") (class "Default")
      (node (ref "J2") (pin "c39") (pinfunction "c39_c39") (pintype "bidirectional"))
      (node (ref "J2") (pin "d36") (pinfunction "d36_d36") (pintype "bidirectional"))
      (node (ref "J2") (pin "d38") (pinfunction "d38_d38") (pintype "bidirectional"))
      (node (ref "J2") (pin "d40") (pinfunction "d40_d40") (pintype "bidirectional"))
      (node (ref "R38") (pin "1") (pinfunction "1_1") (pintype "passive"))
    )
    (net (code "190") (name "P12V0") (class "Default")
      (node (ref "J2") (pin "c35") (pinfunction "c35_c35") (pintype "bidirectional"))
      (node (ref "J2") (pin "c37") (pinfunction "c37_c37") (pintype "bidirectional"))
    )
    (net (code "191") (name "VADJ") (class "Default")
      (node (ref "J2") (pin "e39") (pinfunction "e39_e39") (pintype "bidirectional"))
      (node (ref "J2") (pin "f40") (pinfunction "f40_f40") (pintype "bidirectional"))
      (node (ref "J2") (pin "g39") (pinfunction "g39_g39") (pintype "bidirectional"))
      (node (ref "J2") (pin "h40") (pinfunction "h40_h40") (pintype "bidirectional"))
    )
    (net (code "192") (name "unconnected-(J2-Pada2)") (class "Default")
      (node (ref "J2") (pin "a2") (pinfunction "a2_a2") (pintype "bidirectional+no_connect"))
    )
    (net (code "193") (name "unconnected-(J2-Pada3)") (class "Default")
      (node (ref "J2") (pin "a3") (pinfunction "a3_a3") (pintype "bidirectional+no_connect"))
    )
    (net (code "194") (name "unconnected-(J2-Pada6)") (class "Default")
      (node (ref "J2") (pin "a6") (pinfunction "a6_a6") (pintype "bidirectional+no_connect"))
    )
    (net (code "195") (name "unconnected-(J2-Pada7)") (class "Default")
      (node (ref "J2") (pin "a7") (pinfunction "a7_a7") (pintype "bidirectional+no_connect"))
    )
    (net (code "196") (name "unconnected-(J2-Pada10)") (class "Default")
      (node (ref "J2") (pin "a10") (pinfunction "a10_a10") (pintype "bidirectional+no_connect"))
    )
    (net (code "197") (name "unconnected-(J2-Pada11)") (class "Default")
      (node (ref "J2") (pin "a11") (pinfunction "a11_a11") (pintype "bidirectional+no_connect"))
    )
    (net (code "198") (name "unconnected-(J2-Pada14)") (class "Default")
      (node (ref "J2") (pin "a14") (pinfunction "a14_a14") (pintype "bidirectional+no_connect"))
    )
    (net (code "199") (name "unconnected-(J2-Pada15)") (class "Default")
      (node (ref "J2") (pin "a15") (pinfunction "a15_a15") (pintype "bidirectional+no_connect"))
    )
    (net (code "200") (name "unconnected-(J2-Pada18)") (class "Default")
      (node (ref "J2") (pin "a18") (pinfunction "a18_a18") (pintype "bidirectional+no_connect"))
    )
    (net (code "201") (name "unconnected-(J2-Pada19)") (class "Default")
      (node (ref "J2") (pin "a19") (pinfunction "a19_a19") (pintype "bidirectional+no_connect"))
    )
    (net (code "202") (name "unconnected-(J2-Pada22)") (class "Default")
      (node (ref "J2") (pin "a22") (pinfunction "a22_a22") (pintype "bidirectional+no_connect"))
    )
    (net (code "203") (name "unconnected-(J2-Pada23)") (class "Default")
      (node (ref "J2") (pin "a23") (pinfunction "a23_a23") (pintype "bidirectional+no_connect"))
    )
    (net (code "204") (name "unconnected-(J2-Pada26)") (class "Default")
      (node (ref "J2") (pin "a26") (pinfunction "a26_a26") (pintype "bidirectional+no_connect"))
    )
    (net (code "205") (name "unconnected-(J2-Pada27)") (class "Default")
      (node (ref "J2") (pin "a27") (pinfunction "a27_a27") (pintype "bidirectional+no_connect"))
    )
    (net (code "206") (name "unconnected-(J2-Pada30)") (class "Default")
      (node (ref "J2") (pin "a30") (pinfunction "a30_a30") (pintype "bidirectional+no_connect"))
    )
    (net (code "207") (name "unconnected-(J2-Pada31)") (class "Default")
      (node (ref "J2") (pin "a31") (pinfunction "a31_a31") (pintype "bidirectional+no_connect"))
    )
    (net (code "208") (name "unconnected-(J2-Pada34)") (class "Default")
      (node (ref "J2") (pin "a34") (pinfunction "a34_a34") (pintype "bidirectional+no_connect"))
    )
    (net (code "209") (name "unconnected-(J2-Pada35)") (class "Default")
      (node (ref "J2") (pin "a35") (pinfunction "a35_a35") (pintype "bidirectional+no_connect"))
    )
    (net (code "210") (name "unconnected-(J2-Pada38)") (class "Default")
      (node (ref "J2") (pin "a38") (pinfunction "a38_a38") (pintype "bidirectional+no_connect"))
    )
    (net (code "211") (name "unconnected-(J2-Pada39)") (class "Default")
      (node (ref "J2") (pin "a39") (pinfunction "a39_a39") (pintype "bidirectional+no_connect"))
    )
    (net (code "212") (name "unconnected-(J2-Padb4)") (class "Default")
      (node (ref "J2") (pin "b4") (pinfunction "b4_b4") (pintype "bidirectional+no_connect"))
    )
    (net (code "213") (name "unconnected-(J2-Padb5)") (class "Default")
      (node (ref "J2") (pin "b5") (pinfunction "b5_b5") (pintype "bidirectional+no_connect"))
    )
    (net (code "214") (name "unconnected-(J2-Padb8)") (class "Default")
      (node (ref "J2") (pin "b8") (pinfunction "b8_b8") (pintype "bidirectional+no_connect"))
    )
    (net (code "215") (name "unconnected-(J2-Padb9)") (class "Default")
      (node (ref "J2") (pin "b9") (pinfunction "b9_b9") (pintype "bidirectional+no_connect"))
    )
    (net (code "216") (name "unconnected-(J2-Padb12)") (class "Default")
      (node (ref "J2") (pin "b12") (pinfunction "b12_b12") (pintype "bidirectional+no_connect"))
    )
    (net (code "217") (name "unconnected-(J2-Padb13)") (class "Default")
      (node (ref "J2") (pin "b13") (pinfunction "b13_b13") (pintype "bidirectional+no_connect"))
    )
    (net (code "218") (name "unconnected-(J2-Padb16)") (class "Default")
      (node (ref "J2") (pin "b16") (pinfunction "b16_b16") (pintype "bidirectional+no_connect"))
    )
    (net (code "219") (name "unconnected-(J2-Padb17)") (class "Default")
      (node (ref "J2") (pin "b17") (pinfunction "b17_b17") (pintype "bidirectional+no_connect"))
    )
    (net (code "220") (name "unconnected-(J2-Padb20)") (class "Default")
      (node (ref "J2") (pin "b20") (pinfunction "b20_b20") (pintype "bidirectional+no_connect"))
    )
    (net (code "221") (name "unconnected-(J2-Padb21)") (class "Default")
      (node (ref "J2") (pin "b21") (pinfunction "b21_b21") (pintype "bidirectional+no_connect"))
    )
    (net (code "222") (name "unconnected-(J2-Padb24)") (class "Default")
      (node (ref "J2") (pin "b24") (pinfunction "b24_b24") (pintype "bidirectional+no_connect"))
    )
    (net (code "223") (name "unconnected-(J2-Padb25)") (class "Default")
      (node (ref "J2") (pin "b25") (pinfunction "b25_b25") (pintype "bidirectional+no_connect"))
    )
    (net (code "224") (name "unconnected-(J2-Padb28)") (class "Default")
      (node (ref "J2") (pin "b28") (pinfunction "b28_b28") (pintype "bidirectional+no_connect"))
    )
    (net (code "225") (name "unconnected-(J2-Padb29)") (class "Default")
      (node (ref "J2") (pin "b29") (pinfunction "b29_b29") (pintype "bidirectional+no_connect"))
    )
    (net (code "226") (name "unconnected-(J2-Padb32)") (class "Default")
      (node (ref "J2") (pin "b32") (pinfunction "b32_b32") (pintype "bidirectional+no_connect"))
    )
    (net (code "227") (name "unconnected-(J2-Padb33)") (class "Default")
      (node (ref "J2") (pin "b33") (pinfunction "b33_b33") (pintype "bidirectional+no_connect"))
    )
    (net (code "228") (name "unconnected-(J2-Padb36)") (class "Default")
      (node (ref "J2") (pin "b36") (pinfunction "b36_b36") (pintype "bidirectional+no_connect"))
    )
    (net (code "229") (name "unconnected-(J2-Padb37)") (class "Default")
      (node (ref "J2") (pin "b37") (pinfunction "b37_b37") (pintype "bidirectional+no_connect"))
    )
    (net (code "230") (name "unconnected-(J2-Padb40)") (class "Default")
      (node (ref "J2") (pin "b40") (pinfunction "b40_b40") (pintype "bidirectional+no_connect"))
    )
    (net (code "231") (name "unconnected-(J2-Padc2)") (class "Default")
      (node (ref "J2") (pin "c2") (pinfunction "c2_c2") (pintype "bidirectional+no_connect"))
    )
    (net (code "232") (name "unconnected-(J2-Padc3)") (class "Default")
      (node (ref "J2") (pin "c3") (pinfunction "c3_c3") (pintype "bidirectional+no_connect"))
    )
    (net (code "233") (name "unconnected-(J2-Padc6)") (class "Default")
      (node (ref "J2") (pin "c6") (pinfunction "c6_c6") (pintype "bidirectional+no_connect"))
    )
    (net (code "234") (name "unconnected-(J2-Padc7)") (class "Default")
      (node (ref "J2") (pin "c7") (pinfunction "c7_c7") (pintype "bidirectional+no_connect"))
    )
    (net (code "235") (name "unconnected-(J2-Padd1)") (class "Default")
      (node (ref "J2") (pin "d1") (pinfunction "d1_d1") (pintype "bidirectional+no_connect"))
    )
    (net (code "236") (name "unconnected-(J2-Padd4)") (class "Default")
      (node (ref "J2") (pin "d4") (pinfunction "d4_d4") (pintype "bidirectional+no_connect"))
    )
    (net (code "237") (name "unconnected-(J2-Padd5)") (class "Default")
      (node (ref "J2") (pin "d5") (pinfunction "d5_d5") (pintype "bidirectional+no_connect"))
    )
    (net (code "238") (name "unconnected-(J2-Padd29)") (class "Default")
      (node (ref "J2") (pin "d29") (pinfunction "d29_d29") (pintype "bidirectional+no_connect"))
    )
    (net (code "239") (name "unconnected-(J2-Padd33)") (class "Default")
      (node (ref "J2") (pin "d33") (pinfunction "d33_d33") (pintype "bidirectional+no_connect"))
    )
    (net (code "240") (name "unconnected-(J2-Padd34)") (class "Default")
      (node (ref "J2") (pin "d34") (pinfunction "d34_d34") (pintype "bidirectional+no_connect"))
    )
    (net (code "241") (name "unconnected-(J2-Padj39)") (class "Default")
      (node (ref "J2") (pin "j39") (pinfunction "j39_j39") (pintype "bidirectional"))
    )
    (net (code "242") (name "unconnected-(J2-Padk1)") (class "Default")
      (node (ref "J2") (pin "k1") (pinfunction "k1_k1") (pintype "bidirectional+no_connect"))
    )
    (net (code "243") (name "unconnected-(J2-Padk40)") (class "Default")
      (node (ref "J2") (pin "k40") (pinfunction "k40_k40") (pintype "bidirectional"))
    )
  )
)
